# Accelerometer.net
KiCad netlist of a schematic drawn in Altium Designer
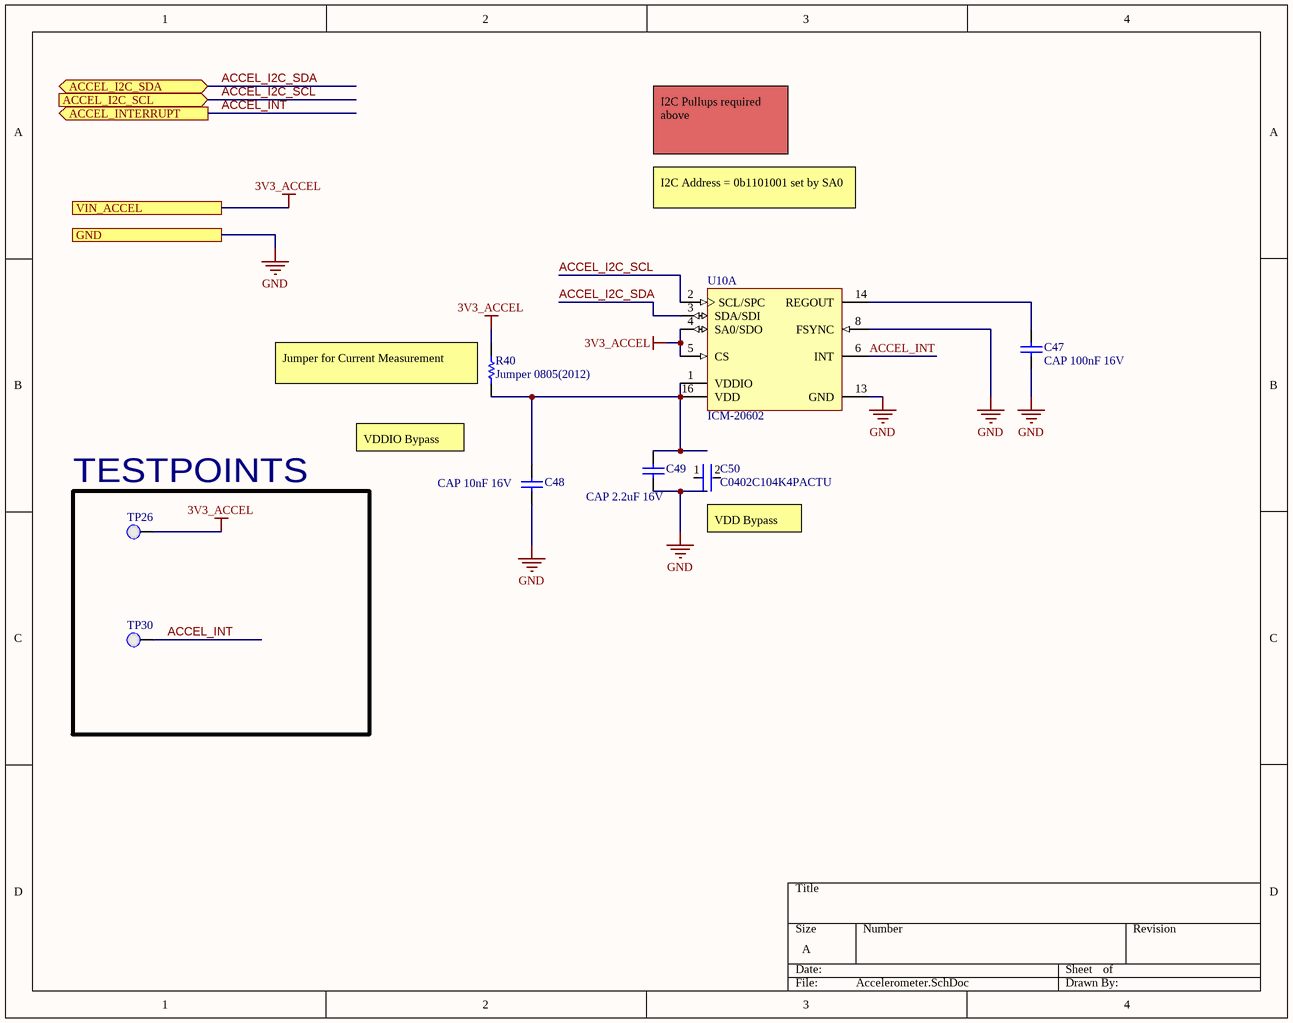
[diagram p0: Accelerometer.SchDoc]

(export (version "E")
  (design (tool "Eeschema 10.0.6"))
  (components
    (comp (ref "C47")
      (value "CAP 100nF 16V")
      (footprint "CAPC0402(1005)60_M")
      (description "CAP 100nF 16V ±10% 0402 (1005 Metric) Thickness 0.6mm SMD")
      (fields (field (name "TOLERANCE") "Â±10%"))
      (libsource (lib "Altium Content Vault") (part "CAP"))
    )
    (comp (ref "C48")
      (value "CAP 10nF 16V")
      (footprint "CAPC0402(1005)33_L")
      (description "CAP 10nF 16V ±10% 0402 (1005 Metric) Thickness 0.33mm SMD")
      (fields (field (name "TOLERANCE") "Â±10%"))
      (libsource (lib "Altium Content Vault") (part "CAP"))
    )
    (comp (ref "C49")
      (value "CAP 2.2uF 16V")
      (footprint "CAPC0603(1608)100_L")
      (description "CAP 2.2uF 16V ±10% 0603 (1608 Metric) Thickness 1mm SMD")
      (fields (field (name "TOLERANCE") "Â±10%"))
      (libsource (lib "Altium Content Vault") (part "CAP"))
    )
    (comp (ref "C50")
      (value "C0402C104K4PACTU")
      (footprint "FP-C0402-BB-MFG")
      (description "CAP CER 0.1UF 16V 10% X5R 0402")
      (fields
        (field (name "TOLERANCE") "0.1")
        (field (name "OCTOPART") "https://octopart.com/c0402c104k4pactu-kemet-8375715")
      )
      (libsource (lib "Altium Content Vault") (part "b4654b650e69147ec39a6b967a45e02"))
    )
    (comp (ref "R40")
      (value "Jumper 0805(2012)")
      (footprint "RESC0805(2012)_N")
      (description "Jumper 0805 (2012 Metric)")
      (fields (field (name "TOLERANCE") "None"))
      (libsource (lib "Altium Content Vault") (part "RES"))
    )
    (comp (ref "TP26")
      (value "0.1\" Pad")
      (footprint "PCBComponent")
      (libsource (lib "Components - 12.02.20 - 18.05") (part "0.1{dblquote} Pad-A.4"))
    )
    (comp (ref "TP30")
      (value "0.1\" Pad")
      (footprint "PCBComponent")
      (libsource (lib "Components - 12.02.20 - 18.05") (part "0.1{dblquote} Pad-A.4"))
    )
    (comp (ref "U10")
      (value "ICM-20602")
      (footprint "INSE-I62-16")
      (fields (field (name "MANUFACTURER") "InvenSense"))
      (libsource (lib "Altium Content Vault") (part "INSE-ICM-20602-16"))
    )
  )
  (nets
    (net (code "1") (name "/ACCEL_I2C_SCL") (class "Default")
      (node (ref "U10") (pin "2") (pinfunction "SCL/SPC_2") (pintype "input"))
    )
    (net (code "2") (name "/ACCEL_I2C_SDA") (class "Default")
      (node (ref "U10") (pin "3") (pinfunction "SDA/SDI_3") (pintype "bidirectional"))
    )
    (net (code "3") (name "/ACCEL_INT") (class "Default")
      (node (ref "TP30") (pin "1") (pinfunction "PAD_1") (pintype "passive"))
      (node (ref "U10") (pin "6") (pinfunction "INT_6") (pintype "open_collector"))
    )
    (net (code "4") (name "3V3_ACCEL") (class "Default")
      (node (ref "R40") (pin "1") (pinfunction "1_1") (pintype "passive"))
      (node (ref "TP26") (pin "1") (pinfunction "PAD_1") (pintype "passive"))
      (node (ref "U10") (pin "4") (pinfunction "SA0/SDO_4") (pintype "bidirectional"))
      (node (ref "U10") (pin "5") (pinfunction "CS_5") (pintype "input"))
    )
    (net (code "5") (name "GND") (class "Default")
      (node (ref "C47") (pin "1") (pinfunction "1_1") (pintype "passive"))
      (node (ref "C48") (pin "1") (pinfunction "1_1") (pintype "passive"))
      (node (ref "C49") (pin "1") (pinfunction "1_1") (pintype "passive"))
      (node (ref "U10") (pin "13") (pinfunction "GND_13") (pintype "power_in"))
      (node (ref "U10") (pin "8") (pinfunction "FSYNC_8") (pintype "input"))
    )
    (net (code "6") (name "Net-(U10A-REGOUT)") (class "Default")
      (node (ref "C47") (pin "2") (pinfunction "2_2") (pintype "passive"))
      (node (ref "U10") (pin "14") (pinfunction "REGOUT_14") (pintype "passive"))
    )
    (net (code "7") (name "Net-(U10A-VDD)") (class "Default")
      (node (ref "C48") (pin "2") (pinfunction "2_2") (pintype "passive"))
      (node (ref "C49") (pin "2") (pinfunction "2_2") (pintype "passive"))
      (node (ref "R40") (pin "2") (pinfunction "2_2") (pintype "passive"))
      (node (ref "U10") (pin "1") (pinfunction "VDDIO_1") (pintype "power_in"))
      (node (ref "U10") (pin "16") (pinfunction "VDD_16") (pintype "power_in"))
    )
    (net (code "8") (name "unconnected-(C50-Pad1)") (class "Default")
      (node (ref "C50") (pin "1") (pinfunction "1_1") (pintype "passive"))
    )
    (net (code "9") (name "unconnected-(C50-Pad2)") (class "Default")
      (node (ref "C50") (pin "2") (pinfunction "2_2") (pintype "passive"))
    )
  )
)
